# Circuit_ECG_Amplifier.net
KiCad netlist of a schematic drawn in Altium Designer
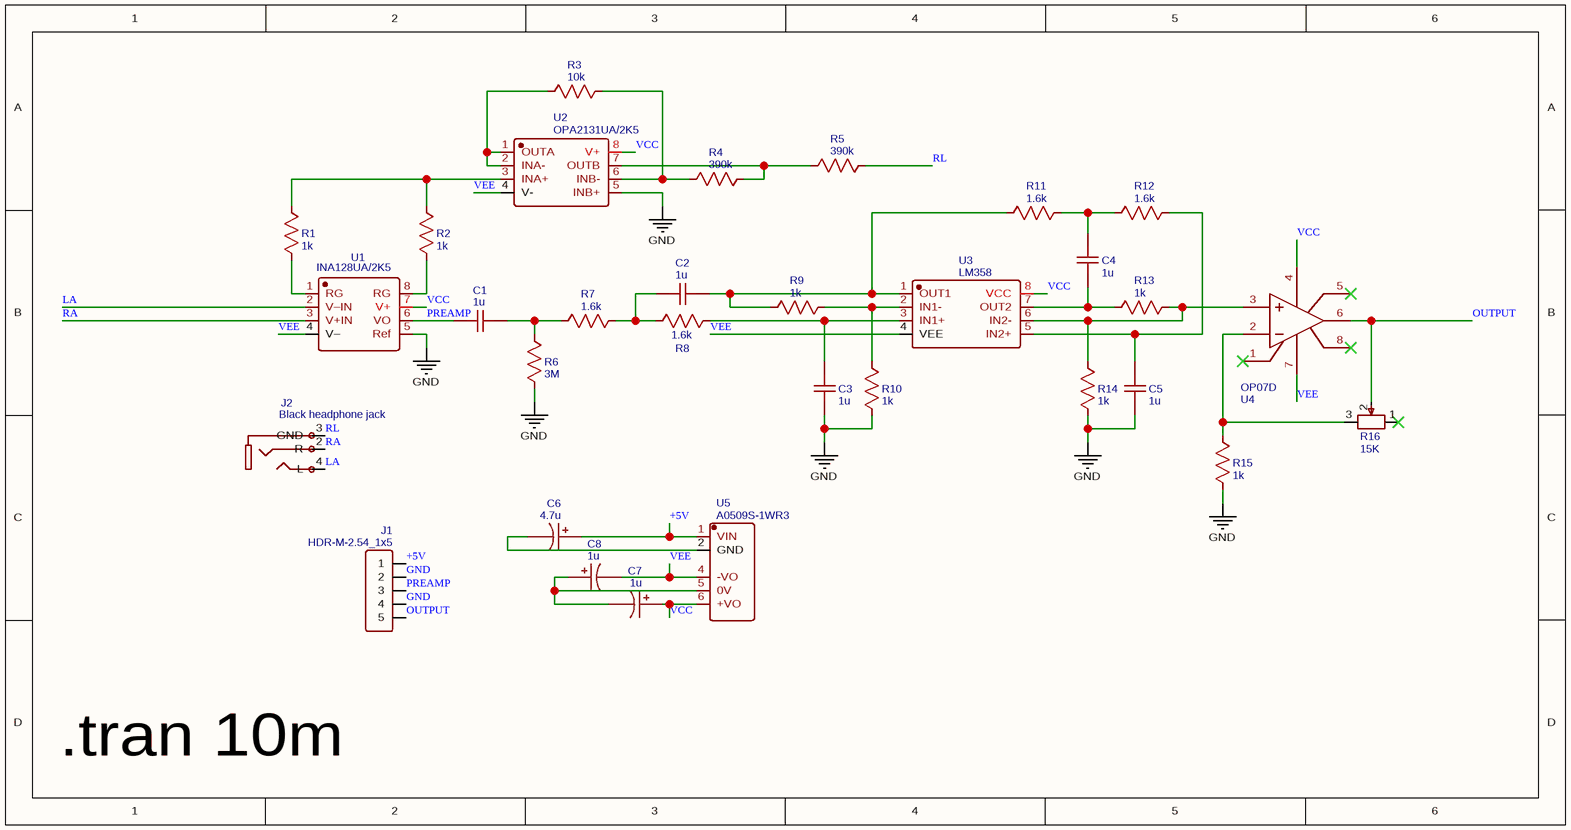
[diagram p0: Circuit_ECG_Amplifier.schdoc]

(export (version "E")
  (design (tool "Eeschema 10.0.6"))
  (components
    (comp (ref "C1")
      (value "1u")
      (fields (field (name "CONTRIBUTOR") "LCEDA_Lib"))
      (libsource (lib "altium-import") (part "root_0_1u_"))
    )
    (comp (ref "C2")
      (value "1u")
      (fields (field (name "CONTRIBUTOR") "LCEDA_Lib"))
      (libsource (lib "altium-import") (part "root_0_1u_"))
    )
    (comp (ref "C3")
      (value "1u")
      (fields (field (name "CONTRIBUTOR") "LCEDA_Lib"))
      (libsource (lib "altium-import") (part "root_3_1u_"))
    )
    (comp (ref "C4")
      (value "1u")
      (fields (field (name "CONTRIBUTOR") "LCEDA_Lib"))
      (libsource (lib "altium-import") (part "root_3_1u_"))
    )
    (comp (ref "C5")
      (value "1u")
      (fields (field (name "CONTRIBUTOR") "LCEDA_Lib"))
      (libsource (lib "altium-import") (part "root_3_1u_"))
    )
    (comp (ref "C6")
      (value "4.7u")
      (fields (field (name "CONTRIBUTOR") "LCEDA_Lib"))
      (libsource (lib "altium-import") (part "root_0_4.7u_"))
    )
    (comp (ref "C7")
      (value "1u")
      (fields (field (name "CONTRIBUTOR") "LCEDA_Lib"))
      (libsource (lib "") (part "root_0_1u__1"))
    )
    (comp (ref "C8")
      (value "1u")
      (fields (field (name "CONTRIBUTOR") "LCEDA_Lib"))
      (libsource (lib "") (part "root_0_1u__2"))
    )
    (comp (ref "J1")
      (value "HDR-M-2.54_1x5")
      (fields (field (name "BOM_SUPPLIER PART") "C358687") (field (name "CONTRIBUTOR") "LCEDA_Lib"))
      (libsource (lib "altium-import") (part "root_0_HDR-M-2.54_1x5_"))
    )
    (comp (ref "J2")
      (value "Black headphone jack")
      (fields (field (name "BOM_SUPPLIER PART") "C18166"))
      (libsource (lib "altium-import") (part "root_0_Black headphone jack_"))
    )
    (comp (ref "R1")
      (value "1k")
      (fields (field (name "CONTRIBUTOR") "LCEDA_Lib"))
      (libsource (lib "altium-import") (part "root_3_1k_"))
    )
    (comp (ref "R2")
      (value "1k")
      (fields (field (name "CONTRIBUTOR") "LCEDA_Lib"))
      (libsource (lib "altium-import") (part "root_3_1k_"))
    )
    (comp (ref "R3")
      (value "10k")
      (fields (field (name "CONTRIBUTOR") "LCEDA_Lib"))
      (libsource (lib "altium-import") (part "root_0_10k_"))
    )
    (comp (ref "R4")
      (value "390k")
      (fields (field (name "CONTRIBUTOR") "LCEDA_Lib"))
      (libsource (lib "altium-import") (part "root_0_390k_"))
    )
    (comp (ref "R5")
      (value "390k")
      (fields (field (name "CONTRIBUTOR") "LCEDA_Lib"))
      (libsource (lib "altium-import") (part "root_0_390k_"))
    )
    (comp (ref "R6")
      (value "3M")
      (fields (field (name "CONTRIBUTOR") "LCEDA_Lib"))
      (libsource (lib "altium-import") (part "root_3_3M_"))
    )
    (comp (ref "R7")
      (value "1.6k")
      (fields (field (name "CONTRIBUTOR") "LCEDA_Lib"))
      (libsource (lib "altium-import") (part "root_0_1.6k_"))
    )
    (comp (ref "R8")
      (value "1.6k")
      (fields (field (name "CONTRIBUTOR") "LCEDA_Lib"))
      (libsource (lib "altium-import") (part "root_0_1.6k_"))
    )
    (comp (ref "R9")
      (value "1k")
      (fields (field (name "CONTRIBUTOR") "LCEDA_Lib"))
      (libsource (lib "altium-import") (part "root_0_1k_"))
    )
    (comp (ref "R10")
      (value "1k")
      (fields (field (name "CONTRIBUTOR") "LCEDA_Lib"))
      (libsource (lib "altium-import") (part "root_3_1k_"))
    )
    (comp (ref "R11")
      (value "1.6k")
      (fields (field (name "CONTRIBUTOR") "LCEDA_Lib"))
      (libsource (lib "altium-import") (part "root_0_1.6k_"))
    )
    (comp (ref "R12")
      (value "1.6k")
      (fields (field (name "CONTRIBUTOR") "LCEDA_Lib"))
      (libsource (lib "altium-import") (part "root_0_1.6k_"))
    )
    (comp (ref "R13")
      (value "1k")
      (fields (field (name "CONTRIBUTOR") "LCEDA_Lib"))
      (libsource (lib "altium-import") (part "root_0_1k_"))
    )
    (comp (ref "R14")
      (value "1k")
      (fields (field (name "CONTRIBUTOR") "LCEDA_Lib"))
      (libsource (lib "altium-import") (part "root_3_1k_"))
    )
    (comp (ref "R15")
      (value "1k")
      (fields (field (name "CONTRIBUTOR") "LCEDA_Lib"))
      (libsource (lib "altium-import") (part "root_3_1k_"))
    )
    (comp (ref "R16")
      (value "15K")
      (fields
        (field (name "BOM_SUPPLIER PART") "C128547")
        (field (name "BOM_MANUFACTURER PART") "VG039NCHXTB153")
        (field (name "CONTRIBUTOR") "LCSC")
      )
      (libsource (lib "altium-import") (part "root_3_15K_"))
    )
    (comp (ref "U1")
      (value "INA128UA/2K5")
      (fields (field (name "BOM_SUPPLIER PART") "C22233"))
      (libsource (lib "altium-import") (part "root_0_INA128UA/2K5_"))
    )
    (comp (ref "U2")
      (value "OPA2131UA/2K5")
      (fields (field (name "BOM_SUPPLIER PART") "C692898") (field (name "CONTRIBUTOR") "LCSC"))
      (libsource (lib "altium-import") (part "root_0_OPA2131UA/2K5_"))
    )
    (comp (ref "U3")
      (value "LM358")
      (fields (field (name "BOM_SUPPLIER PART") "C328566") (field (name "CONTRIBUTOR") "LCSC"))
      (libsource (lib "altium-import") (part "root_0_LM358_"))
    )
    (comp (ref "U4")
      (value "OP07D")
      (fields (field (name "BOM_SUPPLIER PART") "C510565") (field (name "CONTRIBUTOR") "LCSC"))
      (libsource (lib "altium-import") (part "root_0_OP07D_"))
    )
    (comp (ref "U5")
      (value "A0509S-1WR3")
      (fields (field (name "BOM_SUPPLIER PART") "C131900") (field (name "CONTRIBUTOR") "LCSC"))
      (libsource (lib "altium-import") (part "root_0_A0509S-1WR3_"))
    )
  )
  (nets
    (net (code "1") (name "/+5V") (class "Default")
      (node (ref "C6") (pin "1") (pinfunction "1_1") (pintype "passive"))
      (node (ref "J1") (pin "1") (pinfunction "1_1") (pintype "passive"))
      (node (ref "U5") (pin "1") (pinfunction "VIN_1") (pintype "passive"))
    )
    (net (code "2") (name "/LA") (class "Default")
      (node (ref "J2") (pin "4") (pinfunction "L_4") (pintype "passive"))
      (node (ref "U1") (pin "2") (pinfunction "V–IN_2") (pintype "passive"))
    )
    (net (code "3") (name "/OUTPUT") (class "Default")
      (node (ref "J1") (pin "5") (pinfunction "5_5") (pintype "passive"))
      (node (ref "R16") (pin "2") (pinfunction "2_2") (pintype "passive"))
      (node (ref "U4") (pin "6") (pinfunction "OUT_6") (pintype "passive"))
    )
    (net (code "4") (name "/PREAMP") (class "Default")
      (node (ref "C1") (pin "1") (pinfunction "1_1") (pintype "passive"))
      (node (ref "J1") (pin "3") (pinfunction "3_3") (pintype "passive"))
      (node (ref "U1") (pin "6") (pinfunction "VO_6") (pintype "passive"))
    )
    (net (code "5") (name "/RA") (class "Default")
      (node (ref "J2") (pin "2") (pinfunction "R_2") (pintype "passive"))
      (node (ref "U1") (pin "3") (pinfunction "V+IN_3") (pintype "passive"))
    )
    (net (code "6") (name "/RL") (class "Default")
      (node (ref "J2") (pin "3") (pinfunction "GND_3") (pintype "passive"))
      (node (ref "R5") (pin "2") (pinfunction "2_2") (pintype "passive"))
    )
    (net (code "7") (name "/VCC") (class "Default")
      (node (ref "C7") (pin "1") (pinfunction "1_1") (pintype "passive"))
      (node (ref "U1") (pin "7") (pinfunction "V+_7") (pintype "passive"))
      (node (ref "U2") (pin "8") (pinfunction "V+_8") (pintype "passive"))
      (node (ref "U3") (pin "8") (pinfunction "VCC_8") (pintype "passive"))
      (node (ref "U4") (pin "4") (pinfunction "VCC-_4") (pintype "passive"))
      (node (ref "U5") (pin "6") (pinfunction "+VO_6") (pintype "passive"))
    )
    (net (code "8") (name "/VEE") (class "Default")
      (node (ref "C8") (pin "2") (pinfunction "2_2") (pintype "passive"))
      (node (ref "U1") (pin "4") (pinfunction "V–_4") (pintype "passive"))
      (node (ref "U2") (pin "4") (pinfunction "V-_4") (pintype "passive"))
      (node (ref "U3") (pin "4") (pinfunction "VEE_4") (pintype "passive"))
      (node (ref "U4") (pin "7") (pinfunction "VCC+_7") (pintype "passive"))
      (node (ref "U5") (pin "4") (pinfunction "-VO_4") (pintype "passive"))
    )
    (net (code "9") (name "GND") (class "Default")
      (node (ref "C3") (pin "2") (pinfunction "2_2") (pintype "passive"))
      (node (ref "C5") (pin "2") (pinfunction "2_2") (pintype "passive"))
      (node (ref "J1") (pin "2") (pinfunction "2_2") (pintype "passive"))
      (node (ref "J1") (pin "4") (pinfunction "4_4") (pintype "passive"))
      (node (ref "R10") (pin "2") (pinfunction "2_2") (pintype "passive"))
      (node (ref "R14") (pin "2") (pinfunction "2_2") (pintype "passive"))
      (node (ref "R15") (pin "2") (pinfunction "2_2") (pintype "passive"))
      (node (ref "R6") (pin "2") (pinfunction "2_2") (pintype "passive"))
      (node (ref "U1") (pin "5") (pinfunction "Ref_5") (pintype "passive"))
      (node (ref "U2") (pin "5") (pinfunction "INB+_5") (pintype "passive"))
    )
    (net (code "10") (name "Net-(C1-Pad2)") (class "Default")
      (node (ref "C1") (pin "2") (pinfunction "2_2") (pintype "passive"))
      (node (ref "R6") (pin "1") (pinfunction "1_1") (pintype "passive"))
      (node (ref "R7") (pin "1") (pinfunction "1_1") (pintype "passive"))
    )
    (net (code "11") (name "Net-(C2-Pad1)") (class "Default")
      (node (ref "C2") (pin "1") (pinfunction "1_1") (pintype "passive"))
      (node (ref "R7") (pin "2") (pinfunction "2_2") (pintype "passive"))
      (node (ref "R8") (pin "1") (pinfunction "1_1") (pintype "passive"))
    )
    (net (code "12") (name "Net-(C4-Pad1)") (class "Default")
      (node (ref "C4") (pin "1") (pinfunction "1_1") (pintype "passive"))
      (node (ref "R11") (pin "2") (pinfunction "2_2") (pintype "passive"))
      (node (ref "R12") (pin "1") (pinfunction "1_1") (pintype "passive"))
    )
    (net (code "13") (name "Net-(R1-Pad2)") (class "Default")
      (node (ref "R1") (pin "2") (pinfunction "2_2") (pintype "passive"))
      (node (ref "U1") (pin "1") (pinfunction "RG_1") (pintype "passive"))
    )
    (net (code "14") (name "Net-(R2-Pad2)") (class "Default")
      (node (ref "R2") (pin "2") (pinfunction "2_2") (pintype "passive"))
      (node (ref "U1") (pin "8") (pinfunction "RG_8") (pintype "passive"))
    )
    (net (code "15") (name "Net-(U2-INA+)") (class "Default")
      (node (ref "R1") (pin "1") (pinfunction "1_1") (pintype "passive"))
      (node (ref "R2") (pin "1") (pinfunction "1_1") (pintype "passive"))
      (node (ref "U2") (pin "3") (pinfunction "INA+_3") (pintype "passive"))
    )
    (net (code "16") (name "Net-(U2-INA-)") (class "Default")
      (node (ref "R3") (pin "1") (pinfunction "1_1") (pintype "passive"))
      (node (ref "U2") (pin "1") (pinfunction "OUTA_1") (pintype "passive"))
      (node (ref "U2") (pin "2") (pinfunction "INA-_2") (pintype "passive"))
    )
    (net (code "17") (name "Net-(U2-INB-)") (class "Default")
      (node (ref "R3") (pin "2") (pinfunction "2_2") (pintype "passive"))
      (node (ref "R4") (pin "1") (pinfunction "1_1") (pintype "passive"))
      (node (ref "U2") (pin "6") (pinfunction "INB-_6") (pintype "passive"))
    )
    (net (code "18") (name "Net-(U2-OUTB)") (class "Default")
      (node (ref "R4") (pin "2") (pinfunction "2_2") (pintype "passive"))
      (node (ref "R5") (pin "1") (pinfunction "1_1") (pintype "passive"))
      (node (ref "U2") (pin "7") (pinfunction "OUTB_7") (pintype "passive"))
    )
    (net (code "19") (name "Net-(U3-IN1+)") (class "Default")
      (node (ref "C3") (pin "1") (pinfunction "1_1") (pintype "passive"))
      (node (ref "R8") (pin "2") (pinfunction "2_2") (pintype "passive"))
      (node (ref "U3") (pin "3") (pinfunction "IN1+_3") (pintype "passive"))
    )
    (net (code "20") (name "Net-(U3-IN1-)") (class "Default")
      (node (ref "R10") (pin "1") (pinfunction "1_1") (pintype "passive"))
      (node (ref "R9") (pin "2") (pinfunction "2_2") (pintype "passive"))
      (node (ref "U3") (pin "2") (pinfunction "IN1-_2") (pintype "passive"))
    )
    (net (code "21") (name "Net-(U3-IN2+)") (class "Default")
      (node (ref "C5") (pin "1") (pinfunction "1_1") (pintype "passive"))
      (node (ref "R12") (pin "2") (pinfunction "2_2") (pintype "passive"))
      (node (ref "U3") (pin "5") (pinfunction "IN2+_5") (pintype "passive"))
    )
    (net (code "22") (name "Net-(U3-IN2-)") (class "Default")
      (node (ref "R13") (pin "2") (pinfunction "2_2") (pintype "passive"))
      (node (ref "R14") (pin "1") (pinfunction "1_1") (pintype "passive"))
      (node (ref "U3") (pin "6") (pinfunction "IN2-_6") (pintype "passive"))
      (node (ref "U4") (pin "3") (pinfunction "IN+_3") (pintype "passive"))
    )
    (net (code "23") (name "Net-(U3-OUT1)") (class "Default")
      (node (ref "C2") (pin "2") (pinfunction "2_2") (pintype "passive"))
      (node (ref "R11") (pin "1") (pinfunction "1_1") (pintype "passive"))
      (node (ref "R9") (pin "1") (pinfunction "1_1") (pintype "passive"))
      (node (ref "U3") (pin "1") (pinfunction "OUT1_1") (pintype "passive"))
    )
    (net (code "24") (name "Net-(U3-OUT2)") (class "Default")
      (node (ref "C4") (pin "2") (pinfunction "2_2") (pintype "passive"))
      (node (ref "R13") (pin "1") (pinfunction "1_1") (pintype "passive"))
      (node (ref "U3") (pin "7") (pinfunction "OUT2_7") (pintype "passive"))
    )
    (net (code "25") (name "Net-(U4-IN-)") (class "Default")
      (node (ref "R15") (pin "1") (pinfunction "1_1") (pintype "passive"))
      (node (ref "R16") (pin "3") (pinfunction "3_3") (pintype "passive"))
      (node (ref "U4") (pin "2") (pinfunction "IN-_2") (pintype "passive"))
    )
    (net (code "26") (name "Net-(U5-0V)") (class "Default")
      (node (ref "C7") (pin "2") (pinfunction "2_2") (pintype "passive"))
      (node (ref "C8") (pin "1") (pinfunction "1_1") (pintype "passive"))
      (node (ref "U5") (pin "5") (pinfunction "0V_5") (pintype "passive"))
    )
    (net (code "27") (name "Net-(U5-GND)") (class "Default")
      (node (ref "C6") (pin "2") (pinfunction "2_2") (pintype "passive"))
      (node (ref "U5") (pin "2") (pinfunction "GND_2") (pintype "passive"))
    )
    (net (code "28") (name "unconnected-(R16-Pad1)") (class "Default")
      (node (ref "R16") (pin "1") (pinfunction "1_1") (pintype "passive+no_connect"))
    )
    (net (code "29") (name "unconnected-(U4-NC-Pad5)") (class "Default")
      (node (ref "U4") (pin "5") (pinfunction "NC_5") (pintype "passive+no_connect"))
    )
    (net (code "30") (name "unconnected-(U4-OFFSET_N1-Pad1)") (class "Default")
      (node (ref "U4") (pin "1") (pinfunction "OFFSET_N1_1") (pintype "passive+no_connect"))
    )
    (net (code "31") (name "unconnected-(U4-OFFSET_N2-Pad8)") (class "Default")
      (node (ref "U4") (pin "8") (pinfunction "OFFSET_N2_8") (pintype "passive+no_connect"))
    )
  )
)
